# peripherals.net
KiCad netlist of a schematic drawn in Altium Designer
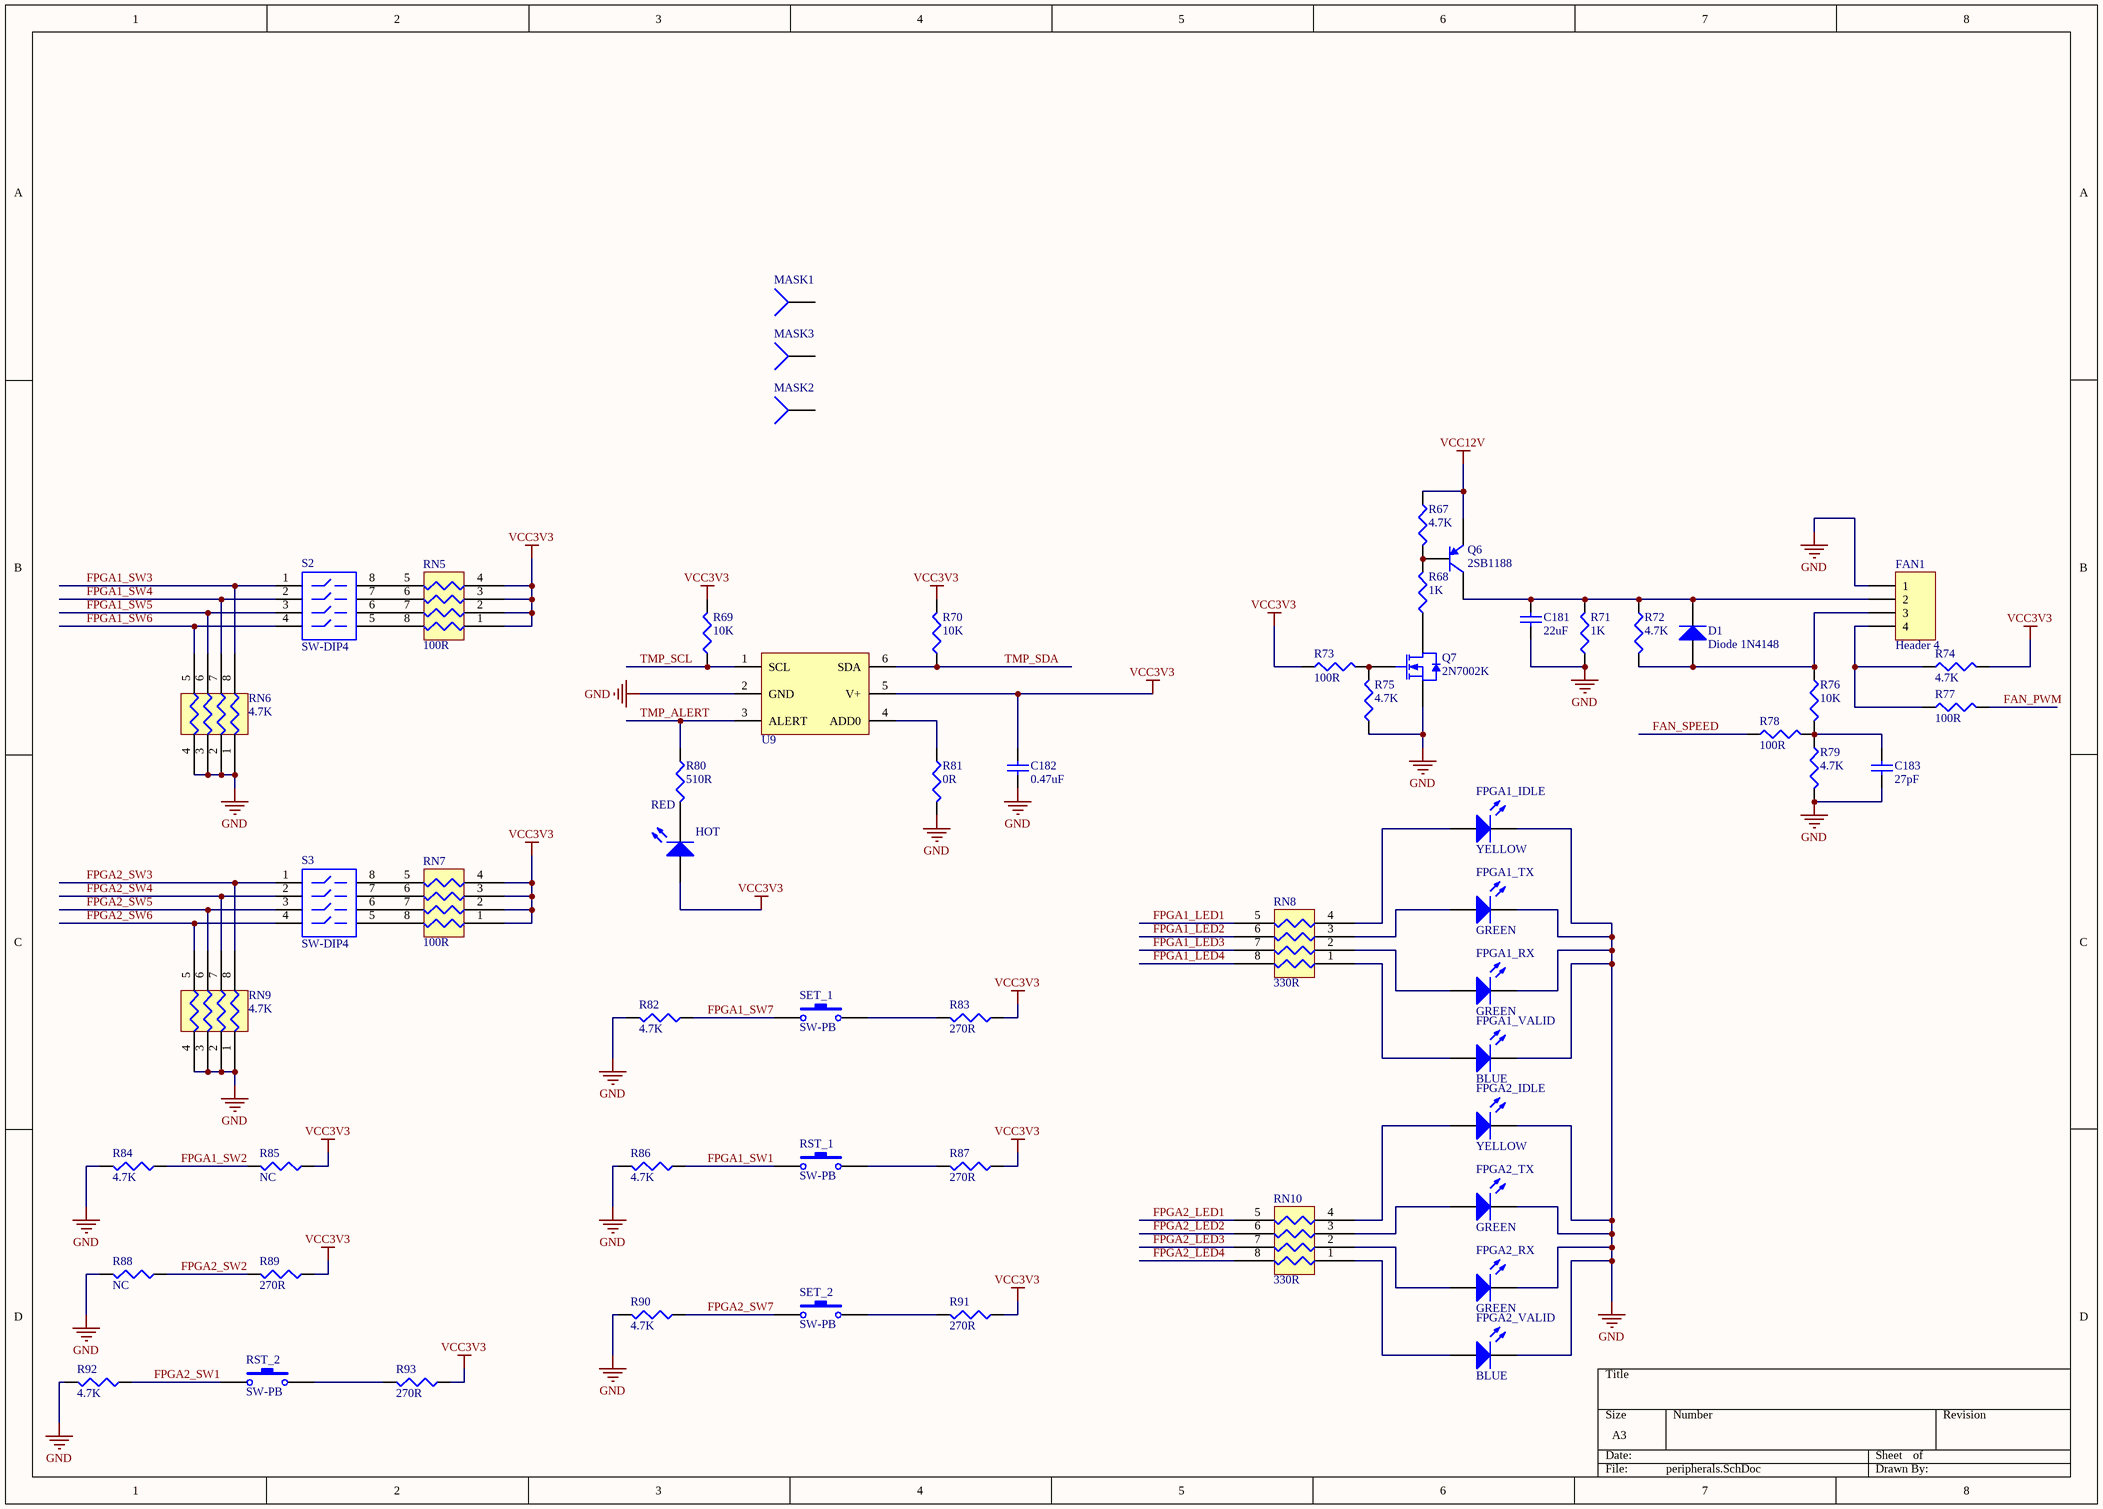
[diagram p0: peripherals.SchDoc]

(export (version "E")
  (design (tool "Eeschema 10.0.6"))
  (components
    (comp (ref "C181")
      (value "22uF")
      (footprint "CAPC3225N")
      (description "Capacitor (Semiconductor SIM Model)")
      (fields (field (name "PUBLISHER") "Altium Limited"))
      (libsource (lib "Miscellaneous Devices") (part "Cap Semi"))
    )
    (comp (ref "C182")
      (value "0.47uF")
      (footprint "CAPC1005N")
      (description "Capacitor (Semiconductor SIM Model)")
      (fields (field (name "PUBLISHER") "Altium Limited"))
      (libsource (lib "Miscellaneous Devices") (part "Cap Semi"))
    )
    (comp (ref "C183")
      (value "27pF")
      (footprint "CAPC1005N")
      (description "Capacitor (Semiconductor SIM Model)")
      (fields (field (name "PUBLISHER") "Altium Limited"))
      (libsource (lib "Miscellaneous Devices") (part "Cap Semi"))
    )
    (comp (ref "D1")
      (value "Diode 1N4148")
      (footprint "CD3216-1206")
      (description "High Conductance Fast Diode")
      (fields (field (name "PUBLISHER") "Altium Limited"))
      (libsource (lib "Miscellaneous Devices") (part "Diode 1N4148"))
    )
    (comp (ref "FAN1")
      (value "Header 4")
      (footprint "4PINFAN")
      (description "Header, 4-Pin")
      (fields (field (name "PUBLISHER") "Altium Limited"))
      (libsource (lib "Miscellaneous Connectors") (part "Header 4"))
    )
    (comp (ref "FPGA1_IDLE")
      (value "YELLOW")
      (footprint "CD1608-0603")
      (description "Typical BLUE SiC LED")
      (fields (field (name "PUBLISHER") "Altium Limited"))
      (libsource (lib "Miscellaneous Devices") (part "LED3"))
    )
    (comp (ref "FPGA1_RX")
      (value "GREEN")
      (footprint "CD1608-0603")
      (description "Typical BLUE SiC LED")
      (fields (field (name "PUBLISHER") "Altium Limited"))
      (libsource (lib "Miscellaneous Devices") (part "LED3"))
    )
    (comp (ref "FPGA1_TX")
      (value "GREEN")
      (footprint "CD1608-0603")
      (description "Typical BLUE SiC LED")
      (fields (field (name "PUBLISHER") "Altium Limited"))
      (libsource (lib "Miscellaneous Devices") (part "LED3"))
    )
    (comp (ref "FPGA1_VALID")
      (value "BLUE")
      (footprint "CD1608-0603")
      (description "Typical BLUE SiC LED")
      (fields (field (name "PUBLISHER") "Altium Limited"))
      (libsource (lib "Miscellaneous Devices") (part "LED3"))
    )
    (comp (ref "FPGA2_IDLE")
      (value "YELLOW")
      (footprint "CD1608-0603")
      (description "Typical BLUE SiC LED")
      (fields (field (name "PUBLISHER") "Altium Limited"))
      (libsource (lib "Miscellaneous Devices") (part "LED3"))
    )
    (comp (ref "FPGA2_RX")
      (value "GREEN")
      (footprint "CD1608-0603")
      (description "Typical BLUE SiC LED")
      (fields (field (name "PUBLISHER") "Altium Limited"))
      (libsource (lib "Miscellaneous Devices") (part "LED3"))
    )
    (comp (ref "FPGA2_TX")
      (value "GREEN")
      (footprint "CD1608-0603")
      (description "Typical BLUE SiC LED")
      (fields (field (name "PUBLISHER") "Altium Limited"))
      (libsource (lib "Miscellaneous Devices") (part "LED3"))
    )
    (comp (ref "FPGA2_VALID")
      (value "BLUE")
      (footprint "CD1608-0603")
      (description "Typical BLUE SiC LED")
      (fields (field (name "PUBLISHER") "Altium Limited"))
      (libsource (lib "Miscellaneous Devices") (part "LED3"))
    )
    (comp (ref "HOT")
      (value "RED")
      (footprint "CD1608-0603")
      (description "Typical BLUE SiC LED")
      (fields (field (name "PUBLISHER") "Altium Limited"))
      (libsource (lib "Miscellaneous Devices") (part "LED3"))
    )
    (comp (ref "MASK1")
      (value "Socket")
      (footprint "MASK")
      (fields (field (name "PUBLISHER") "Altium Limited"))
      (libsource (lib "Miscellaneous Connectors") (part "Socket"))
    )
    (comp (ref "MASK2")
      (value "Socket")
      (footprint "MASK")
      (fields (field (name "PUBLISHER") "Altium Limited"))
      (libsource (lib "Miscellaneous Connectors") (part "Socket"))
    )
    (comp (ref "MASK3")
      (value "Socket")
      (footprint "MASK")
      (fields (field (name "PUBLISHER") "Altium Limited"))
      (libsource (lib "Miscellaneous Connectors") (part "Socket"))
    )
    (comp (ref "Q6")
      (value "2SB1188")
      (footprint "SOT89M")
      (description "PNP Bipolar Transistor")
      (fields (field (name "PUBLISHER") "Altium Limited"))
      (libsource (lib "Miscellaneous Devices") (part "PNP"))
    )
    (comp (ref "Q7")
      (value "2N7002K")
      (footprint "SOT23_N")
      (description "N-channel Enhancement Mode Field-effect Transistor")
      (fields (field (name "PUBLISHER") "Altium Limited"))
      (libsource (lib "Philips Discrete MOSFET - Low Power") (part "2N7002"))
    )
    (comp (ref "R67")
      (value "4.7K")
      (footprint "RESC1005N")
      (description "Resistor")
      (fields (field (name "PUBLISHER") "Altium Limited"))
      (libsource (lib "Miscellaneous Devices") (part "Res3"))
    )
    (comp (ref "R68")
      (value "1K")
      (footprint "RESC1005N")
      (description "Resistor")
      (fields (field (name "PUBLISHER") "Altium Limited"))
      (libsource (lib "Miscellaneous Devices") (part "Res3"))
    )
    (comp (ref "R69")
      (value "10K")
      (footprint "RESC1005N")
      (description "Resistor")
      (fields (field (name "PUBLISHER") "Altium Limited"))
      (libsource (lib "Miscellaneous Devices") (part "Res3"))
    )
    (comp (ref "R70")
      (value "10K")
      (footprint "RESC1005N")
      (description "Resistor")
      (fields (field (name "PUBLISHER") "Altium Limited"))
      (libsource (lib "Miscellaneous Devices") (part "Res3"))
    )
    (comp (ref "R71")
      (value "1K")
      (footprint "RESC1005N")
      (description "Resistor")
      (fields (field (name "PUBLISHER") "Altium Limited"))
      (libsource (lib "Miscellaneous Devices") (part "Res3"))
    )
    (comp (ref "R72")
      (value "4.7K")
      (footprint "RESC1005N")
      (description "Resistor")
      (fields (field (name "PUBLISHER") "Altium Limited"))
      (libsource (lib "Miscellaneous Devices") (part "Res3"))
    )
    (comp (ref "R73")
      (value "100R")
      (footprint "RESC1005N")
      (description "Resistor")
      (fields (field (name "PUBLISHER") "Altium Limited"))
      (libsource (lib "Miscellaneous Devices") (part "Res3"))
    )
    (comp (ref "R74")
      (value "4.7K")
      (footprint "RESC1005N")
      (description "Resistor")
      (fields (field (name "PUBLISHER") "Altium Limited"))
      (libsource (lib "Miscellaneous Devices") (part "Res3"))
    )
    (comp (ref "R75")
      (value "4.7K")
      (footprint "RESC1005N")
      (description "Resistor")
      (fields (field (name "PUBLISHER") "Altium Limited"))
      (libsource (lib "Miscellaneous Devices") (part "Res3"))
    )
    (comp (ref "R76")
      (value "10K")
      (footprint "RESC1005N")
      (description "Resistor")
      (fields (field (name "PUBLISHER") "Altium Limited"))
      (libsource (lib "Miscellaneous Devices") (part "Res3"))
    )
    (comp (ref "R77")
      (value "100R")
      (footprint "RESC1005N")
      (description "Resistor")
      (fields (field (name "PUBLISHER") "Altium Limited"))
      (libsource (lib "Miscellaneous Devices") (part "Res3"))
    )
    (comp (ref "R78")
      (value "100R")
      (footprint "RESC1005N")
      (description "Resistor")
      (fields (field (name "PUBLISHER") "Altium Limited"))
      (libsource (lib "Miscellaneous Devices") (part "Res3"))
    )
    (comp (ref "R79")
      (value "4.7K")
      (footprint "RESC1005N")
      (description "Resistor")
      (fields (field (name "PUBLISHER") "Altium Limited"))
      (libsource (lib "Miscellaneous Devices") (part "Res3"))
    )
    (comp (ref "R80")
      (value "510R")
      (footprint "RESC1005N")
      (description "Resistor")
      (fields (field (name "PUBLISHER") "Altium Limited"))
      (libsource (lib "Miscellaneous Devices") (part "Res3"))
    )
    (comp (ref "R81")
      (value "0R")
      (footprint "RESC1005N")
      (description "Resistor")
      (fields (field (name "PUBLISHER") "Altium Limited"))
      (libsource (lib "Miscellaneous Devices") (part "Res3"))
    )
    (comp (ref "R82")
      (value "4.7K")
      (footprint "RESC1005N")
      (description "Resistor")
      (fields (field (name "PUBLISHER") "Altium Limited"))
      (libsource (lib "Miscellaneous Devices") (part "Res3"))
    )
    (comp (ref "R83")
      (value "270R")
      (footprint "RESC1005N")
      (description "Resistor")
      (fields (field (name "PUBLISHER") "Altium Limited"))
      (libsource (lib "Miscellaneous Devices") (part "Res3"))
    )
    (comp (ref "R84")
      (value "4.7K")
      (footprint "RESC1005N")
      (description "Resistor")
      (fields (field (name "PUBLISHER") "Altium Limited"))
      (libsource (lib "Miscellaneous Devices") (part "Res3"))
    )
    (comp (ref "R85")
      (value "NC")
      (footprint "RESC1005N")
      (description "Resistor")
      (fields (field (name "PUBLISHER") "Altium Limited"))
      (libsource (lib "Miscellaneous Devices") (part "Res3"))
    )
    (comp (ref "R86")
      (value "4.7K")
      (footprint "RESC1005N")
      (description "Resistor")
      (fields (field (name "PUBLISHER") "Altium Limited"))
      (libsource (lib "Miscellaneous Devices") (part "Res3"))
    )
    (comp (ref "R87")
      (value "270R")
      (footprint "RESC1005N")
      (description "Resistor")
      (fields (field (name "PUBLISHER") "Altium Limited"))
      (libsource (lib "Miscellaneous Devices") (part "Res3"))
    )
    (comp (ref "R88")
      (value "NC")
      (footprint "RESC1005N")
      (description "Resistor")
      (fields (field (name "PUBLISHER") "Altium Limited"))
      (libsource (lib "Miscellaneous Devices") (part "Res3"))
    )
    (comp (ref "R89")
      (value "270R")
      (footprint "RESC1005N")
      (description "Resistor")
      (fields (field (name "PUBLISHER") "Altium Limited"))
      (libsource (lib "Miscellaneous Devices") (part "Res3"))
    )
    (comp (ref "R90")
      (value "4.7K")
      (footprint "RESC1005N")
      (description "Resistor")
      (fields (field (name "PUBLISHER") "Altium Limited"))
      (libsource (lib "Miscellaneous Devices") (part "Res3"))
    )
    (comp (ref "R91")
      (value "270R")
      (footprint "RESC1005N")
      (description "Resistor")
      (fields (field (name "PUBLISHER") "Altium Limited"))
      (libsource (lib "Miscellaneous Devices") (part "Res3"))
    )
    (comp (ref "R92")
      (value "4.7K")
      (footprint "RESC1005N")
      (description "Resistor")
      (fields (field (name "PUBLISHER") "Altium Limited"))
      (libsource (lib "Miscellaneous Devices") (part "Res3"))
    )
    (comp (ref "R93")
      (value "270R")
      (footprint "RESC1005N")
      (description "Resistor")
      (fields (field (name "PUBLISHER") "Altium Limited"))
      (libsource (lib "Miscellaneous Devices") (part "Res3"))
    )
    (comp (ref "RN5") (value "100R") (footprint "EXBV8V") (libsource (lib "S6") (part "RES4PACK")))
    (comp (ref "RN6") (value "4.7K") (footprint "EXBV8V") (libsource (lib "") (part "RES4PACK_1")))
    (comp (ref "RN7") (value "100R") (footprint "EXBV8V") (libsource (lib "S6") (part "RES4PACK")))
    (comp (ref "RN8") (value "330R") (footprint "EXBV8V") (libsource (lib "S6") (part "RES4PACK")))
    (comp (ref "RN9") (value "4.7K") (footprint "EXBV8V") (libsource (lib "") (part "RES4PACK_1")))
    (comp (ref "RN10") (value "330R") (footprint "EXBV8V") (libsource (lib "S6") (part "RES4PACK")))
    (comp (ref "RST_1")
      (value "SW-PB")
      (footprint "SKQMA")
      (description "Switch")
      (fields (field (name "PUBLISHER") "Altium Limited"))
      (libsource (lib "Miscellaneous Devices") (part "SW-PB"))
    )
    (comp (ref "RST_2")
      (value "SW-PB")
      (footprint "SKQMA")
      (description "Switch")
      (fields (field (name "PUBLISHER") "Altium Limited"))
      (libsource (lib "Miscellaneous Devices") (part "SW-PB"))
    )
    (comp (ref "S2")
      (value "SW-DIP4")
      (footprint "IPC-SM-782 Section 9.1 SOIC:SO8W")
      (description "DIP Switch")
      (fields (field (name "PUBLISHER") "Altium Limited"))
      (libsource (lib "Miscellaneous Devices") (part "SW-DIP4"))
    )
    (comp (ref "S3")
      (value "SW-DIP4")
      (footprint "SO8W")
      (description "DIP Switch")
      (fields (field (name "PUBLISHER") "Altium Limited"))
      (libsource (lib "Miscellaneous Devices") (part "SW-DIP4"))
    )
    (comp (ref "SET_1")
      (value "SW-PB")
      (footprint "SKQMA")
      (description "Switch")
      (fields (field (name "PUBLISHER") "Altium Limited"))
      (libsource (lib "Miscellaneous Devices") (part "SW-PB"))
    )
    (comp (ref "SET_2")
      (value "SW-PB")
      (footprint "SKQMA")
      (description "Switch")
      (fields (field (name "PUBLISHER") "Altium Limited"))
      (libsource (lib "Miscellaneous Devices") (part "SW-PB"))
    )
    (comp (ref "U9") (value "TMP102") (footprint "SOT563") (libsource (lib "S6_2") (part "TMP102")))
  )
  (nets
    (net (code "1") (name "/FAN_PWM") (class "Default")
      (node (ref "R77") (pin "2") (pinfunction "2_2") (pintype "passive"))
    )
    (net (code "2") (name "/FAN_SPEED") (class "Default")
      (node (ref "R78") (pin "1") (pinfunction "1_1") (pintype "passive"))
    )
    (net (code "3") (name "/FPGA1_LED1") (class "Default")
      (node (ref "RN8") (pin "5") (pinfunction "5_5") (pintype "power_in"))
    )
    (net (code "4") (name "/FPGA1_LED2") (class "Default")
      (node (ref "RN8") (pin "6") (pinfunction "6_6") (pintype "power_in"))
    )
    (net (code "5") (name "/FPGA1_LED3") (class "Default")
      (node (ref "RN8") (pin "7") (pinfunction "7_7") (pintype "power_in"))
    )
    (net (code "6") (name "/FPGA1_LED4") (class "Default")
      (node (ref "RN8") (pin "8") (pinfunction "8_8") (pintype "power_in"))
    )
    (net (code "7") (name "/FPGA1_SW1") (class "Default")
      (node (ref "R86") (pin "1") (pinfunction "1_1") (pintype "passive"))
      (node (ref "RST_1") (pin "1") (pinfunction "1_1") (pintype "passive"))
    )
    (net (code "8") (name "/FPGA1_SW2") (class "Default")
      (node (ref "R84") (pin "1") (pinfunction "1_1") (pintype "passive"))
      (node (ref "R85") (pin "2") (pinfunction "2_2") (pintype "passive"))
    )
    (net (code "9") (name "/FPGA1_SW3") (class "Default")
      (node (ref "RN6") (pin "8") (pinfunction "8_8") (pintype "power_in"))
      (node (ref "S2") (pin "1") (pinfunction "1_1") (pintype "passive"))
    )
    (net (code "10") (name "/FPGA1_SW4") (class "Default")
      (node (ref "RN6") (pin "7") (pinfunction "7_7") (pintype "power_in"))
      (node (ref "S2") (pin "2") (pinfunction "2_2") (pintype "passive"))
    )
    (net (code "11") (name "/FPGA1_SW5") (class "Default")
      (node (ref "RN6") (pin "6") (pinfunction "6_6") (pintype "power_in"))
      (node (ref "S2") (pin "3") (pinfunction "3_3") (pintype "passive"))
    )
    (net (code "12") (name "/FPGA1_SW6") (class "Default")
      (node (ref "RN6") (pin "5") (pinfunction "5_5") (pintype "power_in"))
      (node (ref "S2") (pin "4") (pinfunction "4_4") (pintype "passive"))
    )
    (net (code "13") (name "/FPGA1_SW7") (class "Default")
      (node (ref "R82") (pin "1") (pinfunction "1_1") (pintype "passive"))
      (node (ref "SET_1") (pin "1") (pinfunction "1_1") (pintype "passive"))
    )
    (net (code "14") (name "/FPGA2_LED1") (class "Default")
      (node (ref "RN10") (pin "5") (pinfunction "5_5") (pintype "power_in"))
    )
    (net (code "15") (name "/FPGA2_LED2") (class "Default")
      (node (ref "RN10") (pin "6") (pinfunction "6_6") (pintype "power_in"))
    )
    (net (code "16") (name "/FPGA2_LED3") (class "Default")
      (node (ref "RN10") (pin "7") (pinfunction "7_7") (pintype "power_in"))
    )
    (net (code "17") (name "/FPGA2_LED4") (class "Default")
      (node (ref "RN10") (pin "8") (pinfunction "8_8") (pintype "power_in"))
    )
    (net (code "18") (name "/FPGA2_SW1") (class "Default")
      (node (ref "R92") (pin "1") (pinfunction "1_1") (pintype "passive"))
      (node (ref "RST_2") (pin "1") (pinfunction "1_1") (pintype "passive"))
    )
    (net (code "19") (name "/FPGA2_SW2") (class "Default")
      (node (ref "R88") (pin "1") (pinfunction "1_1") (pintype "passive"))
      (node (ref "R89") (pin "2") (pinfunction "2_2") (pintype "passive"))
    )
    (net (code "20") (name "/FPGA2_SW3") (class "Default")
      (node (ref "RN9") (pin "8") (pinfunction "8_8") (pintype "power_in"))
      (node (ref "S3") (pin "1") (pinfunction "1_1") (pintype "passive"))
    )
    (net (code "21") (name "/FPGA2_SW4") (class "Default")
      (node (ref "RN9") (pin "7") (pinfunction "7_7") (pintype "power_in"))
      (node (ref "S3") (pin "2") (pinfunction "2_2") (pintype "passive"))
    )
    (net (code "22") (name "/FPGA2_SW5") (class "Default")
      (node (ref "RN9") (pin "6") (pinfunction "6_6") (pintype "power_in"))
      (node (ref "S3") (pin "3") (pinfunction "3_3") (pintype "passive"))
    )
    (net (code "23") (name "/FPGA2_SW6") (class "Default")
      (node (ref "RN9") (pin "5") (pinfunction "5_5") (pintype "power_in"))
      (node (ref "S3") (pin "4") (pinfunction "4_4") (pintype "passive"))
    )
    (net (code "24") (name "/FPGA2_SW7") (class "Default")
      (node (ref "R90") (pin "1") (pinfunction "1_1") (pintype "passive"))
      (node (ref "SET_2") (pin "1") (pinfunction "1_1") (pintype "passive"))
    )
    (net (code "25") (name "/TMP_ALERT") (class "Default")
      (node (ref "R80") (pin "1") (pinfunction "1_1") (pintype "passive"))
      (node (ref "U9") (pin "3") (pinfunction "ALERT_3") (pintype "passive"))
    )
    (net (code "26") (name "/TMP_SCL") (class "Default")
      (node (ref "R69") (pin "1") (pinfunction "1_1") (pintype "passive"))
      (node (ref "U9") (pin "1") (pinfunction "SCL_1") (pintype "passive"))
    )
    (net (code "27") (name "/TMP_SDA") (class "Default")
      (node (ref "R70") (pin "1") (pinfunction "1_1") (pintype "passive"))
      (node (ref "U9") (pin "6") (pinfunction "SDA_6") (pintype "passive"))
    )
    (net (code "28") (name "GND") (class "Default")
      (node (ref "C181") (pin "1") (pinfunction "1_1") (pintype "passive"))
      (node (ref "C182") (pin "2") (pinfunction "2_2") (pintype "passive"))
      (node (ref "C183") (pin "2") (pinfunction "2_2") (pintype "passive"))
      (node (ref "FAN1") (pin "1") (pinfunction "1_1") (pintype "passive"))
      (node (ref "FPGA1_IDLE") (pin "2") (pinfunction "K_2") (pintype "passive"))
      (node (ref "FPGA1_RX") (pin "2") (pinfunction "K_2") (pintype "passive"))
      (node (ref "FPGA1_TX") (pin "2") (pinfunction "K_2") (pintype "passive"))
      (node (ref "FPGA1_VALID") (pin "2") (pinfunction "K_2") (pintype "passive"))
      (node (ref "FPGA2_IDLE") (pin "2") (pinfunction "K_2") (pintype "passive"))
      (node (ref "FPGA2_RX") (pin "2") (pinfunction "K_2") (pintype "passive"))
      (node (ref "FPGA2_TX") (pin "2") (pinfunction "K_2") (pintype "passive"))
      (node (ref "FPGA2_VALID") (pin "2") (pinfunction "K_2") (pintype "passive"))
      (node (ref "Q7") (pin "2") (pinfunction "S_2") (pintype "passive"))
      (node (ref "R71") (pin "1") (pinfunction "1_1") (pintype "passive"))
      (node (ref "R75") (pin "1") (pinfunction "1_1") (pintype "passive"))
      (node (ref "R79") (pin "2") (pinfunction "2_2") (pintype "passive"))
      (node (ref "R81") (pin "2") (pinfunction "2_2") (pintype "passive"))
      (node (ref "R82") (pin "2") (pinfunction "2_2") (pintype "passive"))
      (node (ref "R84") (pin "2") (pinfunction "2_2") (pintype "passive"))
      (node (ref "R86") (pin "2") (pinfunction "2_2") (pintype "passive"))
      (node (ref "R88") (pin "2") (pinfunction "2_2") (pintype "passive"))
      (node (ref "R90") (pin "2") (pinfunction "2_2") (pintype "passive"))
      (node (ref "R92") (pin "2") (pinfunction "2_2") (pintype "passive"))
      (node (ref "RN6") (pin "1") (pinfunction "1_1") (pintype "power_in"))
      (node (ref "RN6") (pin "2") (pinfunction "2_2") (pintype "power_in"))
      (node (ref "RN6") (pin "3") (pinfunction "3_3") (pintype "power_in"))
      (node (ref "RN6") (pin "4") (pinfunction "4_4") (pintype "power_in"))
      (node (ref "RN9") (pin "1") (pinfunction "1_1") (pintype "power_in"))
      (node (ref "RN9") (pin "2") (pinfunction "2_2") (pintype "power_in"))
      (node (ref "RN9") (pin "3") (pinfunction "3_3") (pintype "power_in"))
      (node (ref "RN9") (pin "4") (pinfunction "4_4") (pintype "power_in"))
      (node (ref "U9") (pin "2") (pinfunction "GND_2") (pintype "passive"))
    )
    (net (code "29") (name "Net-(C183-Pad1)") (class "Default")
      (node (ref "C183") (pin "1") (pinfunction "1_1") (pintype "passive"))
      (node (ref "R76") (pin "2") (pinfunction "2_2") (pintype "passive"))
      (node (ref "R78") (pin "2") (pinfunction "2_2") (pintype "passive"))
      (node (ref "R79") (pin "1") (pinfunction "1_1") (pintype "passive"))
    )
    (net (code "30") (name "Net-(D1-A)") (class "Default")
      (node (ref "D1") (pin "1") (pinfunction "A_1") (pintype "passive"))
      (node (ref "FAN1") (pin "3") (pinfunction "3_3") (pintype "passive"))
      (node (ref "R72") (pin "2") (pinfunction "2_2") (pintype "passive"))
      (node (ref "R76") (pin "1") (pinfunction "1_1") (pintype "passive"))
    )
    (net (code "31") (name "Net-(D1-K)") (class "Default")
      (node (ref "C181") (pin "2") (pinfunction "2_2") (pintype "passive"))
      (node (ref "D1") (pin "2") (pinfunction "K_2") (pintype "passive"))
      (node (ref "FAN1") (pin "2") (pinfunction "2_2") (pintype "passive"))
      (node (ref "Q6") (pin "1") (pinfunction "C_1") (pintype "passive"))
      (node (ref "R71") (pin "2") (pinfunction "2_2") (pintype "passive"))
      (node (ref "R72") (pin "1") (pinfunction "1_1") (pintype "passive"))
    )
    (net (code "32") (name "Net-(FAN1-Pad4)") (class "Default")
      (node (ref "FAN1") (pin "4") (pinfunction "4_4") (pintype "passive"))
      (node (ref "R74") (pin "1") (pinfunction "1_1") (pintype "passive"))
      (node (ref "R77") (pin "1") (pinfunction "1_1") (pintype "passive"))
    )
    (net (code "33") (name "Net-(FPGA1_IDLE-A)") (class "Default")
      (node (ref "FPGA1_IDLE") (pin "1") (pinfunction "A_1") (pintype "passive"))
      (node (ref "RN8") (pin "4") (pinfunction "4_4") (pintype "power_in"))
    )
    (net (code "34") (name "Net-(FPGA1_RX-A)") (class "Default")
      (node (ref "FPGA1_RX") (pin "1") (pinfunction "A_1") (pintype "passive"))
      (node (ref "RN8") (pin "2") (pinfunction "2_2") (pintype "power_in"))
    )
    (net (code "35") (name "Net-(FPGA1_TX-A)") (class "Default")
      (node (ref "FPGA1_TX") (pin "1") (pinfunction "A_1") (pintype "passive"))
      (node (ref "RN8") (pin "3") (pinfunction "3_3") (pintype "power_in"))
    )
    (net (code "36") (name "Net-(FPGA1_VALID-A)") (class "Default")
      (node (ref "FPGA1_VALID") (pin "1") (pinfunction "A_1") (pintype "passive"))
      (node (ref "RN8") (pin "1") (pinfunction "1_1") (pintype "power_in"))
    )
    (net (code "37") (name "Net-(FPGA2_IDLE-A)") (class "Default")
      (node (ref "FPGA2_IDLE") (pin "1") (pinfunction "A_1") (pintype "passive"))
      (node (ref "RN10") (pin "4") (pinfunction "4_4") (pintype "power_in"))
    )
    (net (code "38") (name "Net-(FPGA2_RX-A)") (class "Default")
      (node (ref "FPGA2_RX") (pin "1") (pinfunction "A_1") (pintype "passive"))
      (node (ref "RN10") (pin "2") (pinfunction "2_2") (pintype "power_in"))
    )
    (net (code "39") (name "Net-(FPGA2_TX-A)") (class "Default")
      (node (ref "FPGA2_TX") (pin "1") (pinfunction "A_1") (pintype "passive"))
      (node (ref "RN10") (pin "3") (pinfunction "3_3") (pintype "power_in"))
    )
    (net (code "40") (name "Net-(FPGA2_VALID-A)") (class "Default")
      (node (ref "FPGA2_VALID") (pin "1") (pinfunction "A_1") (pintype "passive"))
      (node (ref "RN10") (pin "1") (pinfunction "1_1") (pintype "power_in"))
    )
    (net (code "41") (name "Net-(HOT-K)") (class "Default")
      (node (ref "HOT") (pin "2") (pinfunction "K_2") (pintype "passive"))
      (node (ref "R80") (pin "2") (pinfunction "2_2") (pintype "passive"))
    )
    (net (code "42") (name "Net-(Q6-B)") (class "Default")
      (node (ref "Q6") (pin "2") (pinfunction "B_2") (pintype "passive"))
      (node (ref "R67") (pin "2") (pinfunction "2_2") (pintype "passive"))
      (node (ref "R68") (pin "2") (pinfunction "2_2") (pintype "passive"))
    )
    (net (code "43") (name "Net-(Q7-D)") (class "Default")
      (node (ref "Q7") (pin "3") (pinfunction "D_3") (pintype "passive"))
      (node (ref "R68") (pin "1") (pinfunction "1_1") (pintype "passive"))
    )
    (net (code "44") (name "Net-(Q7-G)") (class "Default")
      (node (ref "Q7") (pin "1") (pinfunction "G_1") (pintype "passive"))
      (node (ref "R73") (pin "2") (pinfunction "2_2") (pintype "passive"))
      (node (ref "R75") (pin "2") (pinfunction "2_2") (pintype "passive"))
    )
    (net (code "45") (name "Net-(R83-Pad2)") (class "Default")
      (node (ref "R83") (pin "2") (pinfunction "2_2") (pintype "passive"))
      (node (ref "SET_1") (pin "2") (pinfunction "2_2") (pintype "passive"))
    )
    (net (code "46") (name "Net-(R87-Pad2)") (class "Default")
      (node (ref "R87") (pin "2") (pinfunction "2_2") (pintype "passive"))
      (node (ref "RST_1") (pin "2") (pinfunction "2_2") (pintype "passive"))
    )
    (net (code "47") (name "Net-(R91-Pad2)") (class "Default")
      (node (ref "R91") (pin "2") (pinfunction "2_2") (pintype "passive"))
      (node (ref "SET_2") (pin "2") (pinfunction "2_2") (pintype "passive"))
    )
    (net (code "48") (name "Net-(R93-Pad2)") (class "Default")
      (node (ref "R93") (pin "2") (pinfunction "2_2") (pintype "passive"))
      (node (ref "RST_2") (pin "2") (pinfunction "2_2") (pintype "passive"))
    )
    (net (code "49") (name "Net-(RN5-Pad5)") (class "Default")
      (node (ref "RN5") (pin "5") (pinfunction "5_5") (pintype "power_in"))
      (node (ref "S2") (pin "8") (pinfunction "8_8") (pintype "passive"))
    )
    (net (code "50") (name "Net-(RN5-Pad6)") (class "Default")
      (node (ref "RN5") (pin "6") (pinfunction "6_6") (pintype "power_in"))
      (node (ref "S2") (pin "7") (pinfunction "7_7") (pintype "passive"))
    )
    (net (code "51") (name "Net-(RN5-Pad7)") (class "Default")
      (node (ref "RN5") (pin "7") (pinfunction "7_7") (pintype "power_in"))
      (node (ref "S2") (pin "6") (pinfunction "6_6") (pintype "passive"))
    )
    (net (code "52") (name "Net-(RN5-Pad8)") (class "Default")
      (node (ref "RN5") (pin "8") (pinfunction "8_8") (pintype "power_in"))
      (node (ref "S2") (pin "5") (pinfunction "5_5") (pintype "passive"))
    )
    (net (code "53") (name "Net-(RN7-Pad5)") (class "Default")
      (node (ref "RN7") (pin "5") (pinfunction "5_5") (pintype "power_in"))
      (node (ref "S3") (pin "8") (pinfunction "8_8") (pintype "passive"))
    )
    (net (code "54") (name "Net-(RN7-Pad6)") (class "Default")
      (node (ref "RN7") (pin "6") (pinfunction "6_6") (pintype "power_in"))
      (node (ref "S3") (pin "7") (pinfunction "7_7") (pintype "passive"))
    )
    (net (code "55") (name "Net-(RN7-Pad7)") (class "Default")
      (node (ref "RN7") (pin "7") (pinfunction "7_7") (pintype "power_in"))
      (node (ref "S3") (pin "6") (pinfunction "6_6") (pintype "passive"))
    )
    (net (code "56") (name "Net-(RN7-Pad8)") (class "Default")
      (node (ref "RN7") (pin "8") (pinfunction "8_8") (pintype "power_in"))
      (node (ref "S3") (pin "5") (pinfunction "5_5") (pintype "passive"))
    )
    (net (code "57") (name "Net-(U9-ADD0)") (class "Default")
      (node (ref "R81") (pin "1") (pinfunction "1_1") (pintype "passive"))
      (node (ref "U9") (pin "4") (pinfunction "ADD0_4") (pintype "passive"))
    )
    (net (code "58") (name "VCC3V3") (class "Default")
      (node (ref "C182") (pin "1") (pinfunction "1_1") (pintype "passive"))
      (node (ref "HOT") (pin "1") (pinfunction "A_1") (pintype "passive"))
      (node (ref "R69") (pin "2") (pinfunction "2_2") (pintype "passive"))
      (node (ref "R70") (pin "2") (pinfunction "2_2") (pintype "passive"))
      (node (ref "R73") (pin "1") (pinfunction "1_1") (pintype "passive"))
      (node (ref "R74") (pin "2") (pinfunction "2_2") (pintype "passive"))
      (node (ref "R83") (pin "1") (pinfunction "1_1") (pintype "passive"))
      (node (ref "R85") (pin "1") (pinfunction "1_1") (pintype "passive"))
      (node (ref "R87") (pin "1") (pinfunction "1_1") (pintype "passive"))
      (node (ref "R89") (pin "1") (pinfunction "1_1") (pintype "passive"))
      (node (ref "R91") (pin "1") (pinfunction "1_1") (pintype "passive"))
      (node (ref "R93") (pin "1") (pinfunction "1_1") (pintype "passive"))
      (node (ref "RN5") (pin "1") (pinfunction "1_1") (pintype "power_in"))
      (node (ref "RN5") (pin "2") (pinfunction "2_2") (pintype "power_in"))
      (node (ref "RN5") (pin "3") (pinfunction "3_3") (pintype "power_in"))
      (node (ref "RN5") (pin "4") (pinfunction "4_4") (pintype "power_in"))
      (node (ref "RN7") (pin "1") (pinfunction "1_1") (pintype "power_in"))
      (node (ref "RN7") (pin "2") (pinfunction "2_2") (pintype "power_in"))
      (node (ref "RN7") (pin "3") (pinfunction "3_3") (pintype "power_in"))
      (node (ref "RN7") (pin "4") (pinfunction "4_4") (pintype "power_in"))
      (node (ref "U9") (pin "5") (pinfunction "V+_5") (pintype "passive"))
    )
    (net (code "59") (name "VCC12V") (class "Default")
      (node (ref "Q6") (pin "3") (pinfunction "E_3") (pintype "passive"))
      (node (ref "R67") (pin "1") (pinfunction "1_1") (pintype "passive"))
    )
    (net (code "60") (name "unconnected-(MASK1-Pad1)") (class "Default")
      (node (ref "MASK1") (pin "1") (pinfunction "1_1") (pintype "passive"))
    )
    (net (code "61") (name "unconnected-(MASK2-Pad1)") (class "Default")
      (node (ref "MASK2") (pin "1") (pinfunction "1_1") (pintype "passive"))
    )
    (net (code "62") (name "unconnected-(MASK3-Pad1)") (class "Default")
      (node (ref "MASK3") (pin "1") (pinfunction "1_1") (pintype "passive"))
    )
  )
)
